# STM32.net
KiCad netlist of a schematic drawn in Altium Designer
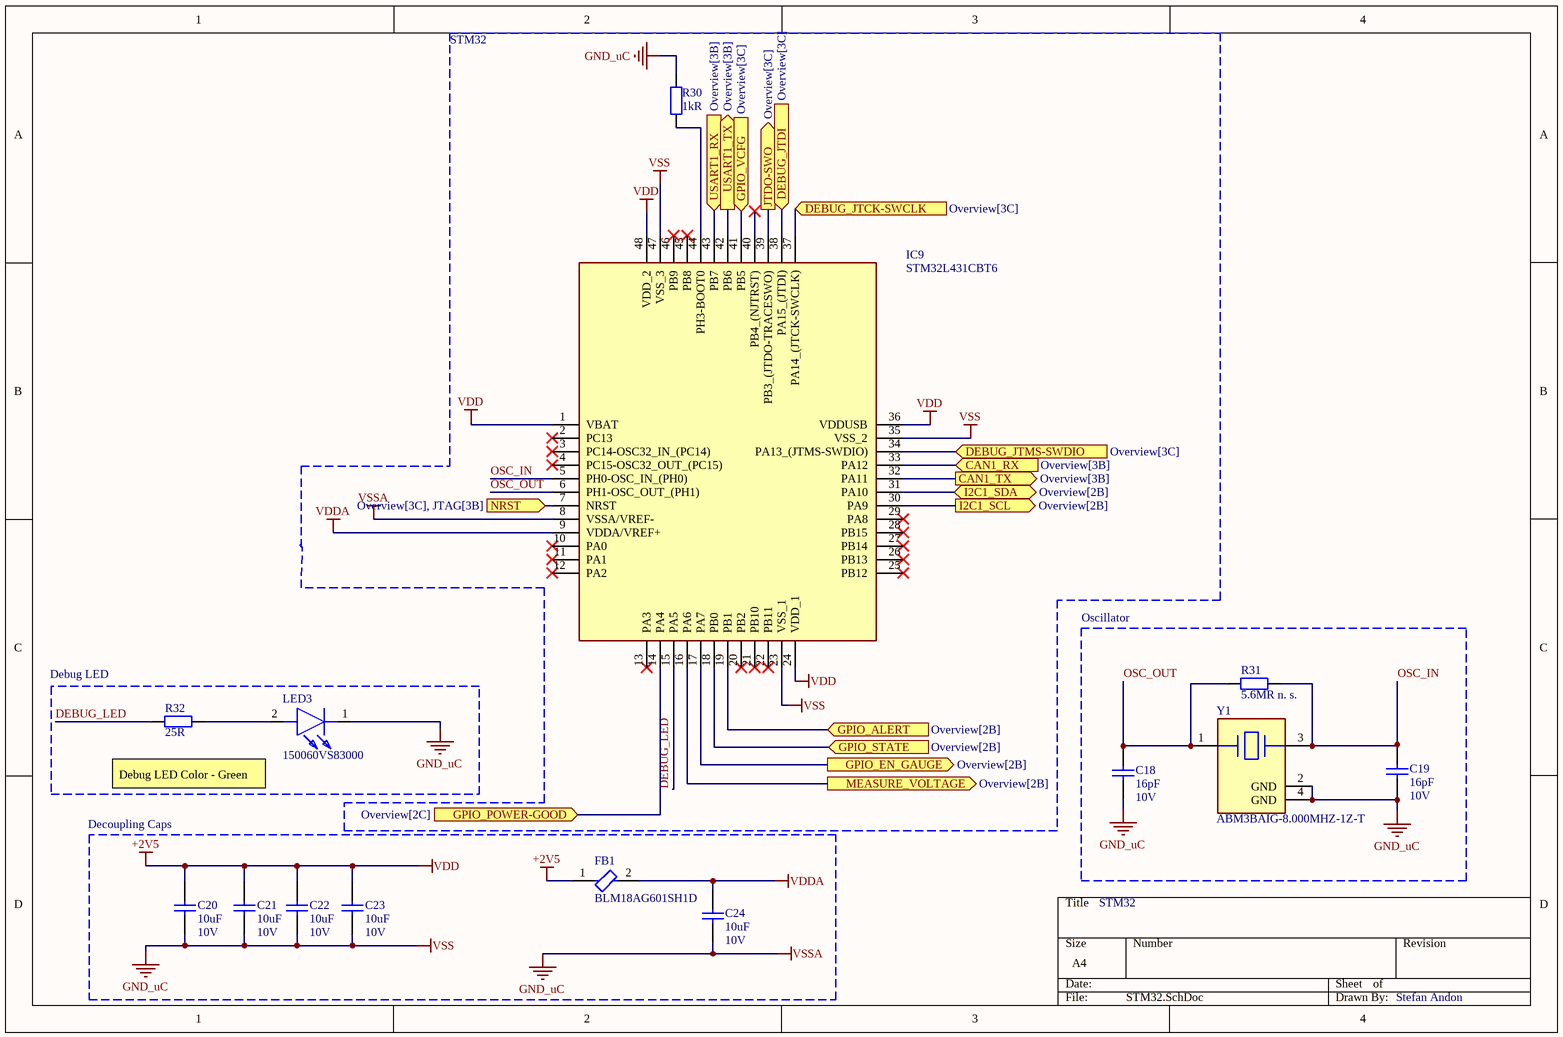
[diagram p0: STM32.SchDoc]

(export (version "E")
  (design (tool "Eeschema 10.0.6"))
  (components
    (comp (ref "C18")
      (value "16pF")
      (footprint "CAP_0603")
      (description "SMD Capacitor")
      (fields
        (field (name "TOLERANCE") "tbd")
        (field (name "VOLTAGE") "10V")
        (field (name "Comment") "Capacitor_SMD")
      )
      (libsource (lib "TUfast e") (part "SMD Capacitor"))
    )
    (comp (ref "C19")
      (value "16pF")
      (footprint "CAP_0603")
      (description "SMD Capacitor")
      (fields
        (field (name "TOLERANCE") "tbd")
        (field (name "VOLTAGE") "10V")
        (field (name "Comment") "Capacitor_SMD")
      )
      (libsource (lib "TUfast e") (part "SMD Capacitor"))
    )
    (comp (ref "C20")
      (value "10uF")
      (footprint "CAP_0603")
      (description "SMD Capacitor")
      (fields
        (field (name "TOLERANCE") "tbd")
        (field (name "VOLTAGE") "10V")
        (field (name "Comment") "Capacitor_SMD")
      )
      (libsource (lib "TUfast e") (part "SMD Capacitor"))
    )
    (comp (ref "C21")
      (value "10uF")
      (footprint "CAP_0603")
      (description "SMD Capacitor")
      (fields
        (field (name "TOLERANCE") "tbd")
        (field (name "VOLTAGE") "10V")
        (field (name "Comment") "Capacitor_SMD")
      )
      (libsource (lib "TUfast e") (part "SMD Capacitor"))
    )
    (comp (ref "C22")
      (value "10uF")
      (footprint "CAP_0603")
      (description "SMD Capacitor")
      (fields
        (field (name "TOLERANCE") "tbd")
        (field (name "VOLTAGE") "10V")
        (field (name "Comment") "Capacitor_SMD")
      )
      (libsource (lib "TUfast e") (part "SMD Capacitor"))
    )
    (comp (ref "C23")
      (value "10uF")
      (footprint "CAP_0603")
      (description "SMD Capacitor")
      (fields
        (field (name "TOLERANCE") "tbd")
        (field (name "VOLTAGE") "10V")
        (field (name "Comment") "Capacitor_SMD")
      )
      (libsource (lib "TUfast e") (part "SMD Capacitor"))
    )
    (comp (ref "C24")
      (value "10uF")
      (footprint "CAP_0603")
      (description "SMD Capacitor")
      (fields
        (field (name "TOLERANCE") "tbd")
        (field (name "VOLTAGE") "10V")
        (field (name "Comment") "Capacitor_SMD")
      )
      (libsource (lib "TUfast e") (part "SMD Capacitor"))
    )
    (comp (ref "FB1")
      (value "BLM18AG601SH1D")
      (footprint "FP-BLM18-0_15-t0_8-MFG")
      (description "Chip Ferrite Bead, 0603, 600Ω @ 100MHz, 0.38Ω, 25%, 500mA")
      (fields (field (name "TOLERANCE") "25%"))
      (libsource (lib "Altium Content Vault") (part "5f30dd21d616792df468990f7003faa"))
    )
    (comp (ref "IC9")
      (value "STM32L431CBT6")
      (footprint "SamacSys:QFP50P900X900X160-48N")
      (description "Integrated Circuit")
      (fields (field (name "MOUSER PART NUMBER") "511-STM32L431CBT6"))
      (libsource (lib "*") (part "STM32L431CBT6"))
    )
    (comp (ref "LED3")
      (value "150060VS83000")
      (footprint "SamacSys:150060VS83000")
      (description "LED")
      (libsource (lib "*") (part "150060VS83000"))
    )
    (comp (ref "R30")
      (value "1kR")
      (footprint "RES_0603")
      (fields
        (field (name "TOLERANCE") "tbd")
        (field (name "POWER") "7W")
        (field (name "Comment") "Resistor_SMD")
      )
      (libsource (lib "") (part "Resistor_1"))
    )
    (comp (ref "R31")
      (value "5.6MR n. s.")
      (footprint "RES_0603")
      (fields
        (field (name "TOLERANCE") "tbd")
        (field (name "POWER") "7W")
        (field (name "Comment") "Resistor_SMD")
      )
      (libsource (lib "TUfast e") (part "Resistor"))
    )
    (comp (ref "R32")
      (value "25R")
      (footprint "RES_0603")
      (fields
        (field (name "TOLERANCE") "tbd")
        (field (name "POWER") "7W")
        (field (name "Comment") "Resistor_SMD")
      )
      (libsource (lib "TUfast e") (part "Resistor"))
    )
    (comp (ref "Y1")
      (value "ABM3BAIG-8.000MHZ-1Z-T")
      (footprint "FP-ABM3BAIG-MFG")
      (description "CRYSTAL 8.0000MHZ 18PF SMD")
      (libsource (lib "Altium Content Vault") (part "3dd7ae69e6a56028198fd7abc02d048"))
    )
  )
  (nets
    (net (code "1") (name "+2V5") (class "Default")
      (node (ref "C20") (pin "1") (pinfunction "1_1") (pintype "passive"))
      (node (ref "C21") (pin "1") (pinfunction "1_1") (pintype "passive"))
      (node (ref "C22") (pin "1") (pinfunction "1_1") (pintype "passive"))
      (node (ref "C23") (pin "1") (pinfunction "1_1") (pintype "passive"))
      (node (ref "FB1") (pin "1") (pinfunction "1_1") (pintype "passive"))
      (node (ref "IC9") (pin "1") (pinfunction "VBAT_1") (pintype "power_in"))
      (node (ref "IC9") (pin "24") (pinfunction "VDD_1_24") (pintype "power_in"))
      (node (ref "IC9") (pin "36") (pinfunction "VDDUSB_36") (pintype "power_in"))
      (node (ref "IC9") (pin "48") (pinfunction "VDD_2_48") (pintype "power_in"))
    )
    (net (code "2") (name "/CAN1_RX") (class "Default")
      (node (ref "IC9") (pin "33") (pinfunction "PA12_33") (pintype "passive"))
    )
    (net (code "3") (name "/CAN1_TX") (class "Default")
      (node (ref "IC9") (pin "32") (pinfunction "PA11_32") (pintype "passive"))
    )
    (net (code "4") (name "/DEBUG_JTCK-SWCLK") (class "Default")
      (node (ref "IC9") (pin "37") (pinfunction "PA14_(JTCK-SWCLK)_37") (pintype "passive"))
    )
    (net (code "5") (name "/DEBUG_JTDI") (class "Default")
      (node (ref "IC9") (pin "38") (pinfunction "PA15_(JTDI)_38") (pintype "passive"))
    )
    (net (code "6") (name "/DEBUG_JTMS-SWDIO") (class "Default")
      (node (ref "IC9") (pin "34") (pinfunction "PA13_(JTMS-SWDIO)_34") (pintype "passive"))
    )
    (net (code "7") (name "/DEBUG_LED") (class "Default")
      (node (ref "IC9") (pin "15") (pinfunction "PA5_15") (pintype "passive"))
      (node (ref "R32") (pin "2") (pinfunction "2_2") (pintype "passive"))
    )
    (net (code "8") (name "/GPIO_ALERT") (class "Default")
      (node (ref "IC9") (pin "19") (pinfunction "PB1_19") (pintype "passive"))
    )
    (net (code "9") (name "/GPIO_EN_GAUGE") (class "Default")
      (node (ref "IC9") (pin "17") (pinfunction "PA7_17") (pintype "passive"))
    )
    (net (code "10") (name "/GPIO_POWER-GOOD") (class "Default")
      (node (ref "IC9") (pin "14") (pinfunction "PA4_14") (pintype "passive"))
    )
    (net (code "11") (name "/GPIO_STATE") (class "Default")
      (node (ref "IC9") (pin "18") (pinfunction "PB0_18") (pintype "passive"))
    )
    (net (code "12") (name "/GPIO_VCFG") (class "Default")
      (node (ref "IC9") (pin "41") (pinfunction "PB5_41") (pintype "passive"))
    )
    (net (code "13") (name "/I2C1_SCL") (class "Default")
      (node (ref "IC9") (pin "30") (pinfunction "PA9_30") (pintype "passive"))
    )
    (net (code "14") (name "/I2C1_SDA") (class "Default")
      (node (ref "IC9") (pin "31") (pinfunction "PA10_31") (pintype "passive"))
    )
    (net (code "15") (name "/JTDO-SWO") (class "Default")
      (node (ref "IC9") (pin "39") (pinfunction "PB3_(JTDO-TRACESWO)_39") (pintype "passive"))
    )
    (net (code "16") (name "/MEASURE_VOLTAGE") (class "Default")
      (node (ref "IC9") (pin "16") (pinfunction "PA6_16") (pintype "passive"))
    )
    (net (code "17") (name "/NRST") (class "Default")
      (node (ref "IC9") (pin "7") (pinfunction "NRST_7") (pintype "passive"))
    )
    (net (code "18") (name "/OSC_IN") (class "Default")
      (node (ref "C19") (pin "1") (pinfunction "1_1") (pintype "passive"))
      (node (ref "IC9") (pin "5") (pinfunction "PH0-OSC_IN_(PH0)_5") (pintype "passive"))
      (node (ref "R31") (pin "1") (pinfunction "1_1") (pintype "passive"))
      (node (ref "Y1") (pin "3") (pinfunction "3_3") (pintype "passive"))
    )
    (net (code "19") (name "/OSC_OUT") (class "Default")
      (node (ref "C18") (pin "1") (pinfunction "1_1") (pintype "passive"))
      (node (ref "IC9") (pin "6") (pinfunction "PH1-OSC_OUT_(PH1)_6") (pintype "passive"))
      (node (ref "R31") (pin "2") (pinfunction "2_2") (pintype "passive"))
      (node (ref "Y1") (pin "1") (pinfunction "1_1") (pintype "passive"))
    )
    (net (code "20") (name "/USART1_RX") (class "Default")
      (node (ref "IC9") (pin "43") (pinfunction "PB7_43") (pintype "passive"))
    )
    (net (code "21") (name "/USART1_TX") (class "Default")
      (node (ref "IC9") (pin "42") (pinfunction "PB6_42") (pintype "passive"))
    )
    (net (code "22") (name "GND_uC") (class "Default")
      (node (ref "C18") (pin "2") (pinfunction "2_2") (pintype "passive"))
      (node (ref "C19") (pin "2") (pinfunction "2_2") (pintype "passive"))
      (node (ref "C20") (pin "2") (pinfunction "2_2") (pintype "passive"))
      (node (ref "C21") (pin "2") (pinfunction "2_2") (pintype "passive"))
      (node (ref "C22") (pin "2") (pinfunction "2_2") (pintype "passive"))
      (node (ref "C23") (pin "2") (pinfunction "2_2") (pintype "passive"))
      (node (ref "C24") (pin "2") (pinfunction "2_2") (pintype "passive"))
      (node (ref "IC9") (pin "23") (pinfunction "VSS_1_23") (pintype "power_in"))
      (node (ref "IC9") (pin "35") (pinfunction "VSS_2_35") (pintype "power_in"))
      (node (ref "IC9") (pin "47") (pinfunction "VSS_3_47") (pintype "power_in"))
      (node (ref "IC9") (pin "8") (pinfunction "VSSA/VREF-_8") (pintype "power_in"))
      (node (ref "LED3") (pin "1") (pinfunction "K_1") (pintype "passive"))
      (node (ref "R30") (pin "1") (pinfunction "1_1") (pintype "passive"))
      (node (ref "Y1") (pin "2") (pinfunction "GND_2") (pintype "power_in"))
      (node (ref "Y1") (pin "4") (pinfunction "GND_4") (pintype "power_in"))
    )
    (net (code "23") (name "Net-(IC9-PH3-BOOT0)") (class "Default")
      (node (ref "IC9") (pin "44") (pinfunction "PH3-BOOT0_44") (pintype "passive"))
      (node (ref "R30") (pin "2") (pinfunction "2_2") (pintype "passive"))
    )
    (net (code "24") (name "Net-(LED3-A)") (class "Default")
      (node (ref "LED3") (pin "2") (pinfunction "A_2") (pintype "passive"))
      (node (ref "R32") (pin "1") (pinfunction "1_1") (pintype "passive"))
    )
    (net (code "25") (name "VDDA") (class "Default")
      (node (ref "C24") (pin "1") (pinfunction "1_1") (pintype "passive"))
      (node (ref "FB1") (pin "2") (pinfunction "2_2") (pintype "passive"))
      (node (ref "IC9") (pin "9") (pinfunction "VDDA/VREF+_9") (pintype "power_in"))
    )
    (net (code "26") (name "unconnected-(IC9-PA0-Pad10)") (class "Default")
      (node (ref "IC9") (pin "10") (pinfunction "PA0_10") (pintype "passive+no_connect"))
    )
    (net (code "27") (name "unconnected-(IC9-PA1-Pad11)") (class "Default")
      (node (ref "IC9") (pin "11") (pinfunction "PA1_11") (pintype "passive+no_connect"))
    )
    (net (code "28") (name "unconnected-(IC9-PA2-Pad12)") (class "Default")
      (node (ref "IC9") (pin "12") (pinfunction "PA2_12") (pintype "passive+no_connect"))
    )
    (net (code "29") (name "unconnected-(IC9-PA3-Pad13)") (class "Default")
      (node (ref "IC9") (pin "13") (pinfunction "PA3_13") (pintype "passive+no_connect"))
    )
    (net (code "30") (name "unconnected-(IC9-PA8-Pad29)") (class "Default")
      (node (ref "IC9") (pin "29") (pinfunction "PA8_29") (pintype "passive+no_connect"))
    )
    (net (code "31") (name "unconnected-(IC9-PB2-Pad20)") (class "Default")
      (node (ref "IC9") (pin "20") (pinfunction "PB2_20") (pintype "passive+no_connect"))
    )
    (net (code "32") (name "unconnected-(IC9-PB4_(NJTRST)-Pad40)") (class "Default")
      (node (ref "IC9") (pin "40") (pinfunction "PB4_(NJTRST)_40") (pintype "passive+no_connect"))
    )
    (net (code "33") (name "unconnected-(IC9-PB8-Pad45)") (class "Default")
      (node (ref "IC9") (pin "45") (pinfunction "PB8_45") (pintype "passive+no_connect"))
    )
    (net (code "34") (name "unconnected-(IC9-PB9-Pad46)") (class "Default")
      (node (ref "IC9") (pin "46") (pinfunction "PB9_46") (pintype "passive+no_connect"))
    )
    (net (code "35") (name "unconnected-(IC9-PB10-Pad21)") (class "Default")
      (node (ref "IC9") (pin "21") (pinfunction "PB10_21") (pintype "passive+no_connect"))
    )
    (net (code "36") (name "unconnected-(IC9-PB11-Pad22)") (class "Default")
      (node (ref "IC9") (pin "22") (pinfunction "PB11_22") (pintype "passive+no_connect"))
    )
    (net (code "37") (name "unconnected-(IC9-PB12-Pad25)") (class "Default")
      (node (ref "IC9") (pin "25") (pinfunction "PB12_25") (pintype "passive+no_connect"))
    )
    (net (code "38") (name "unconnected-(IC9-PB13-Pad26)") (class "Default")
      (node (ref "IC9") (pin "26") (pinfunction "PB13_26") (pintype "passive+no_connect"))
    )
    (net (code "39") (name "unconnected-(IC9-PB14-Pad27)") (class "Default")
      (node (ref "IC9") (pin "27") (pinfunction "PB14_27") (pintype "passive+no_connect"))
    )
    (net (code "40") (name "unconnected-(IC9-PB15-Pad28)") (class "Default")
      (node (ref "IC9") (pin "28") (pinfunction "PB15_28") (pintype "passive+no_connect"))
    )
    (net (code "41") (name "unconnected-(IC9-PC13-Pad2)") (class "Default")
      (node (ref "IC9") (pin "2") (pinfunction "PC13_2") (pintype "passive+no_connect"))
    )
    (net (code "42") (name "unconnected-(IC9-PC14-OSC32_IN_(PC14)-Pad3)") (class "Default")
      (node (ref "IC9") (pin "3") (pinfunction "PC14-OSC32_IN_(PC14)_3") (pintype "passive+no_connect"))
    )
    (net (code "43") (name "unconnected-(IC9-PC15-OSC32_OUT_(PC15)-Pad4)") (class "Default")
      (node (ref "IC9") (pin "4") (pinfunction "PC15-OSC32_OUT_(PC15)_4") (pintype "passive+no_connect"))
    )
  )
)
